# stopwatch.net
KiCad netlist of a schematic drawn in EasyEDA
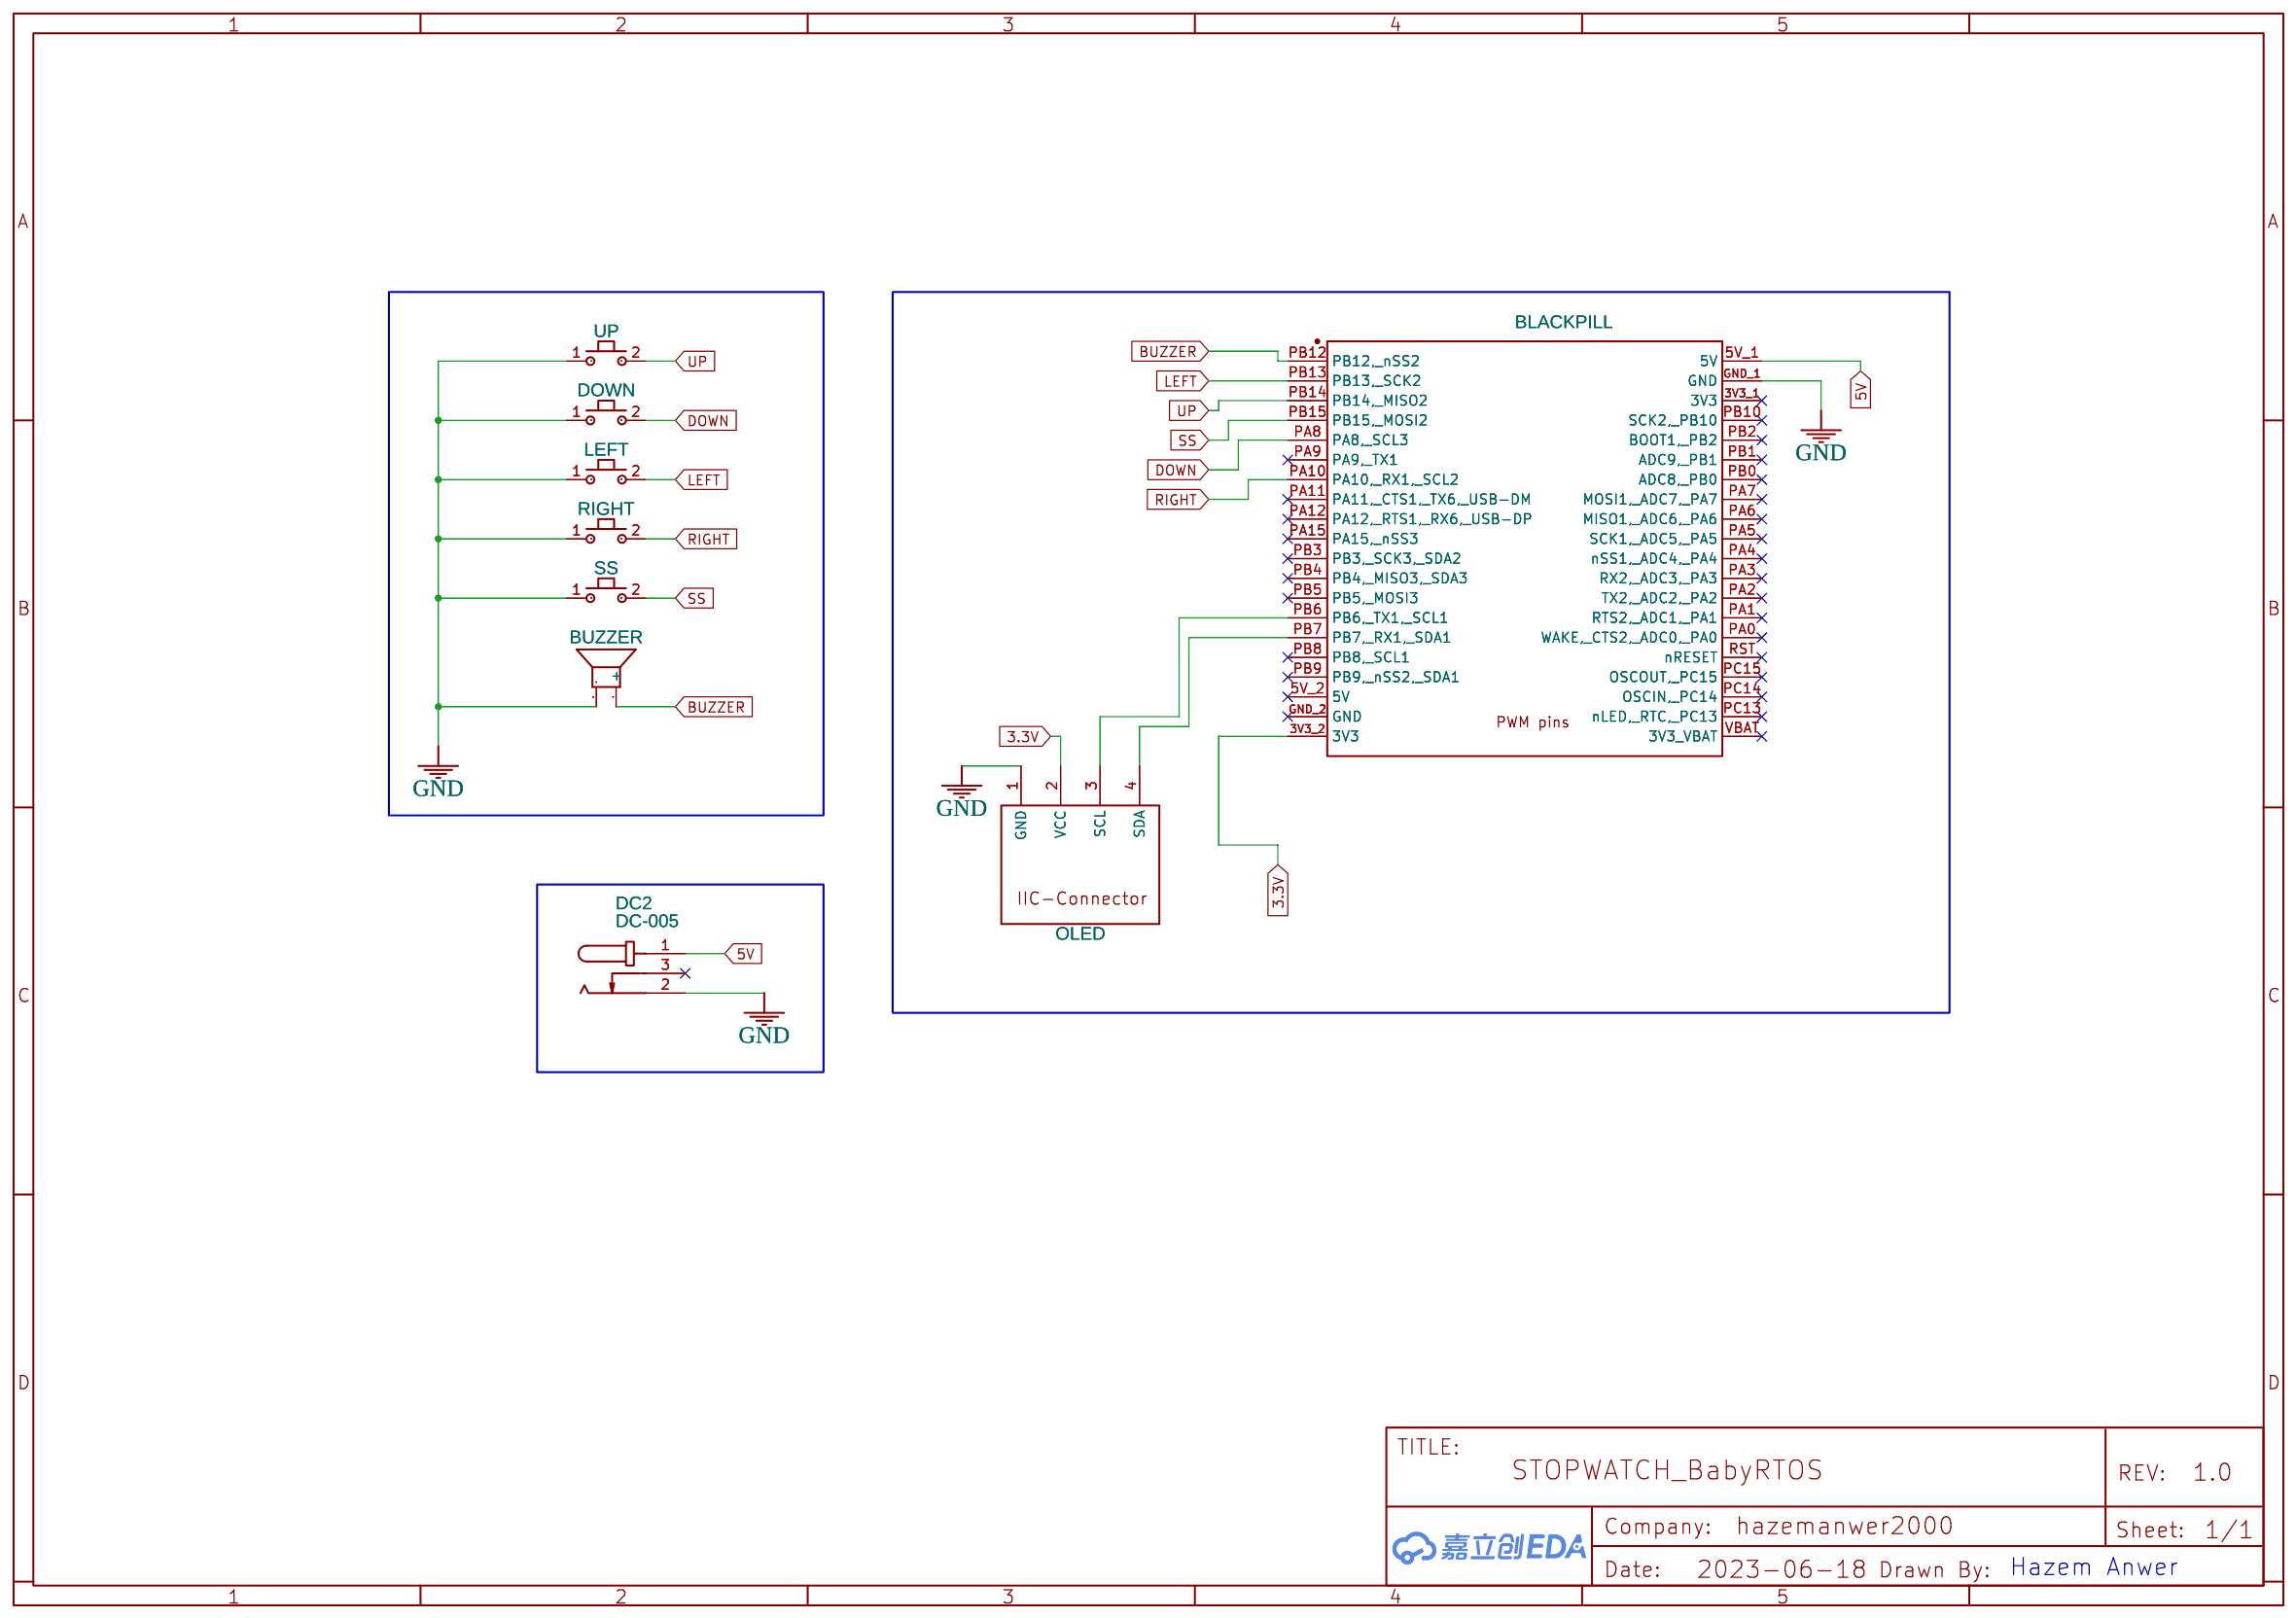
[diagram p0: schematic sheet]

(export (version "E")
  (design (tool "Eeschema 10.0.6"))
  (components
    (comp (ref "BLACKPILL")
      (value "STM32F401CC Black Pill Module")
      (fields (field (name "BOM_Manufacturer Part") "Blackpill") (field (name "BOM_Supplier Part") "NA"))
      (libsource (lib "") (part "STM32F401CC Black Pill Module"))
    )
    (comp (ref "BUZZER")
      (value "BUZZER-12X9")
      (fields
        (field (name "BOM_Manufacturer Part") "buzzer-12X9")
        (field (name "BOM_Supplier Part") "C9900016920")
      )
      (libsource (lib "") (part "BUZZER-12X9"))
    )
    (comp (ref "DC2")
      (value "DC-005")
      (fields (field (name "BOM_Supplier Part") "C9900004933"))
      (libsource (lib "") (part "DC-005"))
    )
    (comp (ref "DOWN")
      (value "CMI625501D06")
      (fields (field (name "BOM_Supplier Part") "C400265"))
      (libsource (lib "") (part "CMI625501D06_1"))
    )
    (comp (ref "LEFT")
      (value "CMI625501D06")
      (fields (field (name "BOM_Supplier Part") "C400265"))
      (libsource (lib "") (part "CMI625501D06_2"))
    )
    (comp (ref "OLED")
      (value "0.96OLED_4P_MODULE_JX")
      (fields (field (name "BOM_Supplier Part") "C9900004566"))
      (libsource (lib "") (part "0.96OLED_4P_MODULE_JX"))
    )
    (comp (ref "RIGHT")
      (value "CMI625501D06")
      (fields (field (name "BOM_Supplier Part") "C400265"))
      (libsource (lib "") (part "CMI625501D06"))
    )
    (comp (ref "SS")
      (value "CMI625501D06")
      (fields (field (name "BOM_Supplier Part") "C400265"))
      (libsource (lib "") (part "CMI625501D06_4"))
    )
    (comp (ref "UP")
      (value "CMI625501D06")
      (fields (field (name "BOM_Supplier Part") "C400265"))
      (libsource (lib "") (part "CMI625501D06_3"))
    )
  )
  (nets
    (net (code "1") (name "3.3V") (class "Default")
      (node (ref "BLACKPILL") (pin "3V3_2") (pinfunction "3V3_3V3_2") (pintype "unspecified"))
      (node (ref "OLED") (pin "2") (pinfunction "VCC_2") (pintype "unspecified"))
    )
    (net (code "2") (name "5V") (class "Default")
      (node (ref "BLACKPILL") (pin "5V_1") (pinfunction "5V_5V_1") (pintype "unspecified"))
      (node (ref "DC2") (pin "1") (pinfunction "1_1") (pintype "unspecified"))
    )
    (net (code "3") (name "BUZZER") (class "Default")
      (node (ref "BLACKPILL") (pin "PB12") (pinfunction "PB12,_nSS2_PB12") (pintype "unspecified"))
      (node (ref "BUZZER") (pin "1") (pinfunction "+_1") (pintype "unspecified"))
    )
    (net (code "4") (name "DOWN") (class "Default")
      (node (ref "BLACKPILL") (pin "PA8") (pinfunction "PA8,_SCL3_PA8") (pintype "unspecified"))
      (node (ref "DOWN") (pin "2") (pinfunction "2_2") (pintype "unspecified"))
    )
    (net (code "5") (name "GND") (class "Default")
      (node (ref "BLACKPILL") (pin "GND_1") (pinfunction "GND_GND_1") (pintype "unspecified"))
      (node (ref "BUZZER") (pin "2") (pinfunction "2_2") (pintype "unspecified"))
      (node (ref "DC2") (pin "2") (pinfunction "2_2") (pintype "unspecified"))
      (node (ref "DOWN") (pin "1") (pinfunction "1_1") (pintype "unspecified"))
      (node (ref "LEFT") (pin "1") (pinfunction "1_1") (pintype "unspecified"))
      (node (ref "OLED") (pin "1") (pinfunction "GND_1") (pintype "unspecified"))
      (node (ref "RIGHT") (pin "1") (pinfunction "1_1") (pintype "unspecified"))
      (node (ref "SS") (pin "1") (pinfunction "1_1") (pintype "unspecified"))
      (node (ref "UP") (pin "1") (pinfunction "1_1") (pintype "unspecified"))
    )
    (net (code "6") (name "LEFT") (class "Default")
      (node (ref "BLACKPILL") (pin "PB13") (pinfunction "PB13,_SCK2_PB13") (pintype "unspecified"))
      (node (ref "LEFT") (pin "2") (pinfunction "2_2") (pintype "unspecified"))
    )
    (net (code "7") (name "Net-(BLACKPILL-PB6,_TX1,_SCL1)") (class "Default")
      (node (ref "BLACKPILL") (pin "PB6") (pinfunction "PB6,_TX1,_SCL1_PB6") (pintype "unspecified"))
      (node (ref "OLED") (pin "3") (pinfunction "SCL_3") (pintype "unspecified"))
    )
    (net (code "8") (name "Net-(BLACKPILL-PB7,_RX1,_SDA1)") (class "Default")
      (node (ref "BLACKPILL") (pin "PB7") (pinfunction "PB7,_RX1,_SDA1_PB7") (pintype "unspecified"))
      (node (ref "OLED") (pin "4") (pinfunction "SDA_4") (pintype "unspecified"))
    )
    (net (code "9") (name "RIGHT") (class "Default")
      (node (ref "BLACKPILL") (pin "PA10") (pinfunction "PA10,_RX1,_SCL2_PA10") (pintype "unspecified"))
      (node (ref "RIGHT") (pin "2") (pinfunction "2_2") (pintype "unspecified"))
    )
    (net (code "10") (name "SS") (class "Default")
      (node (ref "BLACKPILL") (pin "PB15") (pinfunction "PB15,_MOSI2_PB15") (pintype "unspecified"))
      (node (ref "SS") (pin "2") (pinfunction "2_2") (pintype "unspecified"))
    )
    (net (code "11") (name "UP") (class "Default")
      (node (ref "BLACKPILL") (pin "PB14") (pinfunction "PB14,_MISO2_PB14") (pintype "unspecified"))
      (node (ref "UP") (pin "2") (pinfunction "2_2") (pintype "unspecified"))
    )
    (net (code "12") (name "unconnected-(BLACKPILL-3V3-Pad3V3_1)") (class "Default")
      (node (ref "BLACKPILL") (pin "3V3_1") (pinfunction "3V3_3V3_1") (pintype "unspecified+no_connect"))
    )
    (net (code "13") (name "unconnected-(BLACKPILL-3V3_VBAT-PadVBAT)") (class "Default")
      (node (ref "BLACKPILL") (pin "VBAT") (pinfunction "3V3_VBAT_VBAT") (pintype "unspecified+no_connect"))
    )
    (net (code "14") (name "unconnected-(BLACKPILL-5V-Pad5V_2)") (class "Default")
      (node (ref "BLACKPILL") (pin "5V_2") (pinfunction "5V_5V_2") (pintype "unspecified+no_connect"))
    )
    (net (code "15") (name "unconnected-(BLACKPILL-ADC8,_PB0-PadPB0)") (class "Default")
      (node (ref "BLACKPILL") (pin "PB0") (pinfunction "ADC8,_PB0_PB0") (pintype "unspecified+no_connect"))
    )
    (net (code "16") (name "unconnected-(BLACKPILL-ADC9,_PB1-PadPB1)") (class "Default")
      (node (ref "BLACKPILL") (pin "PB1") (pinfunction "ADC9,_PB1_PB1") (pintype "unspecified+no_connect"))
    )
    (net (code "17") (name "unconnected-(BLACKPILL-BOOT1,_PB2-PadPB2)") (class "Default")
      (node (ref "BLACKPILL") (pin "PB2") (pinfunction "BOOT1,_PB2_PB2") (pintype "unspecified+no_connect"))
    )
    (net (code "18") (name "unconnected-(BLACKPILL-GND-PadGND_2)") (class "Default")
      (node (ref "BLACKPILL") (pin "GND_2") (pinfunction "GND_GND_2") (pintype "unspecified+no_connect"))
    )
    (net (code "19") (name "unconnected-(BLACKPILL-MISO1,_ADC6,_PA6-PadPA6)") (class "Default")
      (node (ref "BLACKPILL") (pin "PA6") (pinfunction "MISO1,_ADC6,_PA6_PA6") (pintype "unspecified+no_connect"))
    )
    (net (code "20") (name "unconnected-(BLACKPILL-MOSI1,_ADC7,_PA7-PadPA7)") (class "Default")
      (node (ref "BLACKPILL") (pin "PA7") (pinfunction "MOSI1,_ADC7,_PA7_PA7") (pintype "unspecified+no_connect"))
    )
    (net (code "21") (name "unconnected-(BLACKPILL-OSCIN,_PC14-PadPC14)") (class "Default")
      (node (ref "BLACKPILL") (pin "PC14") (pinfunction "OSCIN,_PC14_PC14") (pintype "unspecified+no_connect"))
    )
    (net (code "22") (name "unconnected-(BLACKPILL-OSCOUT,_PC15-PadPC15)") (class "Default")
      (node (ref "BLACKPILL") (pin "PC15") (pinfunction "OSCOUT,_PC15_PC15") (pintype "unspecified+no_connect"))
    )
    (net (code "23") (name "unconnected-(BLACKPILL-PA9,_TX1-PadPA9)") (class "Default")
      (node (ref "BLACKPILL") (pin "PA9") (pinfunction "PA9,_TX1_PA9") (pintype "unspecified+no_connect"))
    )
    (net (code "24") (name "unconnected-(BLACKPILL-PA11,_CTS1,_TX6,_USB-DM-PadPA11)") (class "Default")
      (node (ref "BLACKPILL") (pin "PA11") (pinfunction "PA11,_CTS1,_TX6,_USB-DM_PA11") (pintype "unspecified+no_connect"))
    )
    (net (code "25") (name "unconnected-(BLACKPILL-PA12,_RTS1,_RX6,_USB-DP-PadPA12)") (class "Default")
      (node (ref "BLACKPILL") (pin "PA12") (pinfunction "PA12,_RTS1,_RX6,_USB-DP_PA12") (pintype "unspecified+no_connect"))
    )
    (net (code "26") (name "unconnected-(BLACKPILL-PA15,_nSS3-PadPA15)") (class "Default")
      (node (ref "BLACKPILL") (pin "PA15") (pinfunction "PA15,_nSS3_PA15") (pintype "unspecified+no_connect"))
    )
    (net (code "27") (name "unconnected-(BLACKPILL-PB3,_SCK3,_SDA2-PadPB3)") (class "Default")
      (node (ref "BLACKPILL") (pin "PB3") (pinfunction "PB3,_SCK3,_SDA2_PB3") (pintype "unspecified+no_connect"))
    )
    (net (code "28") (name "unconnected-(BLACKPILL-PB4,_MISO3,_SDA3-PadPB4)") (class "Default")
      (node (ref "BLACKPILL") (pin "PB4") (pinfunction "PB4,_MISO3,_SDA3_PB4") (pintype "unspecified+no_connect"))
    )
    (net (code "29") (name "unconnected-(BLACKPILL-PB5,_MOSI3-PadPB5)") (class "Default")
      (node (ref "BLACKPILL") (pin "PB5") (pinfunction "PB5,_MOSI3_PB5") (pintype "unspecified+no_connect"))
    )
    (net (code "30") (name "unconnected-(BLACKPILL-PB8,_SCL1-PadPB8)") (class "Default")
      (node (ref "BLACKPILL") (pin "PB8") (pinfunction "PB8,_SCL1_PB8") (pintype "unspecified+no_connect"))
    )
    (net (code "31") (name "unconnected-(BLACKPILL-PB9,_nSS2,_SDA1-PadPB9)") (class "Default")
      (node (ref "BLACKPILL") (pin "PB9") (pinfunction "PB9,_nSS2,_SDA1_PB9") (pintype "unspecified+no_connect"))
    )
    (net (code "32") (name "unconnected-(BLACKPILL-RTS2,_ADC1,_PA1-PadPA1)") (class "Default")
      (node (ref "BLACKPILL") (pin "PA1") (pinfunction "RTS2,_ADC1,_PA1_PA1") (pintype "unspecified+no_connect"))
    )
    (net (code "33") (name "unconnected-(BLACKPILL-RX2,_ADC3,_PA3-PadPA3)") (class "Default")
      (node (ref "BLACKPILL") (pin "PA3") (pinfunction "RX2,_ADC3,_PA3_PA3") (pintype "unspecified+no_connect"))
    )
    (net (code "34") (name "unconnected-(BLACKPILL-SCK1,_ADC5,_PA5-PadPA5)") (class "Default")
      (node (ref "BLACKPILL") (pin "PA5") (pinfunction "SCK1,_ADC5,_PA5_PA5") (pintype "unspecified+no_connect"))
    )
    (net (code "35") (name "unconnected-(BLACKPILL-SCK2,_PB10-PadPB10)") (class "Default")
      (node (ref "BLACKPILL") (pin "PB10") (pinfunction "SCK2,_PB10_PB10") (pintype "unspecified+no_connect"))
    )
    (net (code "36") (name "unconnected-(BLACKPILL-TX2,_ADC2,_PA2-PadPA2)") (class "Default")
      (node (ref "BLACKPILL") (pin "PA2") (pinfunction "TX2,_ADC2,_PA2_PA2") (pintype "unspecified+no_connect"))
    )
    (net (code "37") (name "unconnected-(BLACKPILL-WAKE,_CTS2,_ADC0,_PA0-PadPA0)") (class "Default")
      (node (ref "BLACKPILL") (pin "PA0") (pinfunction "WAKE,_CTS2,_ADC0,_PA0_PA0") (pintype "unspecified+no_connect"))
    )
    (net (code "38") (name "unconnected-(BLACKPILL-nLED,_RTC,_PC13-PadPC13)") (class "Default")
      (node (ref "BLACKPILL") (pin "PC13") (pinfunction "nLED,_RTC,_PC13_PC13") (pintype "unspecified+no_connect"))
    )
    (net (code "39") (name "unconnected-(BLACKPILL-nRESET-PadRST)") (class "Default")
      (node (ref "BLACKPILL") (pin "RST") (pinfunction "nRESET_RST") (pintype "unspecified+no_connect"))
    )
    (net (code "40") (name "unconnected-(BLACKPILL-nSS1,_ADC4,_PA4-PadPA4)") (class "Default")
      (node (ref "BLACKPILL") (pin "PA4") (pinfunction "nSS1,_ADC4,_PA4_PA4") (pintype "unspecified+no_connect"))
    )
    (net (code "41") (name "unconnected-(DC2-Pad3)") (class "Default")
      (node (ref "DC2") (pin "3") (pinfunction "3_3") (pintype "unspecified+no_connect"))
    )
  )
)
